# Display.net
KiCad netlist of a schematic drawn in Altium Designer
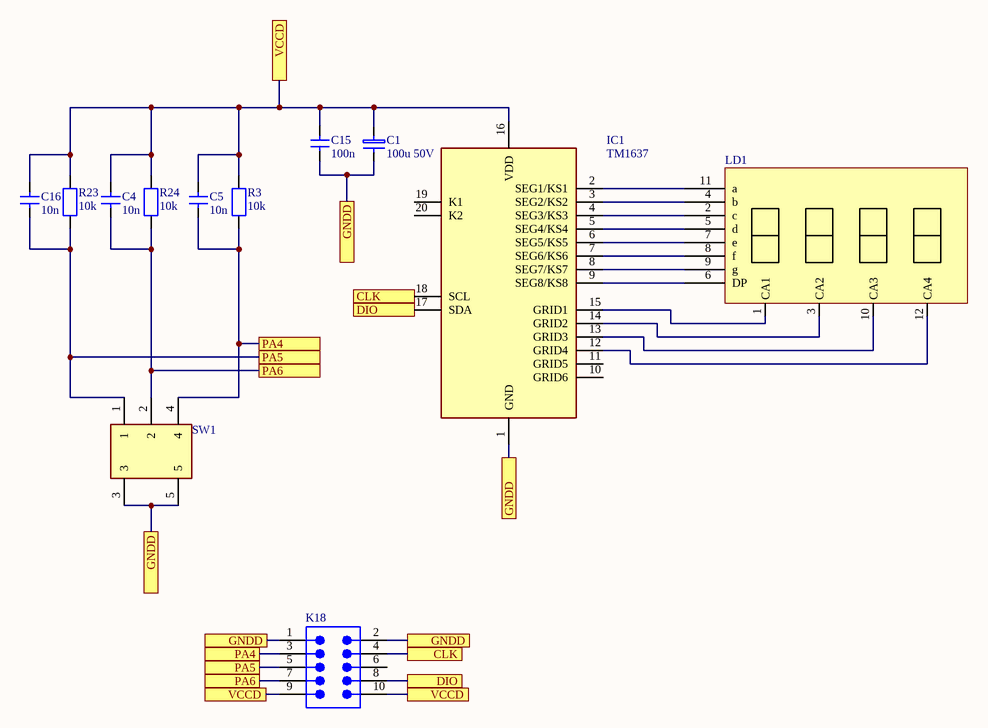
[diagram p0: Display.SchDoc]

(export (version "E")
  (design (tool "Eeschema 10.0.6"))
  (components
    (comp (ref "C1")
      (value "100u 50V")
      (footprint "CAPACITOR100UF")
      (description "860010683032 WCAP-ATG8 Aluminum Electrolytic Capacitors")
      (fields (field (name "TOLERANCE") "20%"))
      (libsource (lib "Soldeerstation Schematic") (part "CapacitorPol"))
    )
    (comp (ref "C4")
      (value "10n")
      (footprint "CAPACITOR10NF")
      (description "CAP CER 10000PF 50V X7R 0805")
      (fields (field (name "TOLERANCE") "10%"))
      (libsource (lib "Soldeerstation Schematic") (part "Capacitor"))
    )
    (comp (ref "C5")
      (value "10n")
      (footprint "CAPACITOR10NF")
      (description "CAP CER 10000PF 50V X7R 0805")
      (fields (field (name "TOLERANCE") "10%"))
      (libsource (lib "Soldeerstation Schematic") (part "Capacitor"))
    )
    (comp (ref "C15")
      (value "100n")
      (footprint "Capacitor100nf")
      (description "CAP CER 10000PF 50V X7R 0805")
      (fields (field (name "TOLERANCE") "10%"))
      (libsource (lib "Soldeerstation Schematic") (part "Capacitor"))
    )
    (comp (ref "C16")
      (value "10n")
      (footprint "CAPACITOR10NF")
      (description "CAP CER 10000PF 50V X7R 0805")
      (fields (field (name "TOLERANCE") "10%"))
      (libsource (lib "Soldeerstation Schematic") (part "Capacitor"))
    )
    (comp (ref "IC1")
      (value "TM1637")
      (footprint "Soldeerstation PCB:TM1637")
      (description "LED Drive Control Special Circuit")
      (fields (field (name "MF") "Titan Micro Electronics"))
      (libsource (lib "Soldeerstation Schematic") (part "TM1637"))
    )
    (comp (ref "K18")
      (value "61231020621")
      (footprint "[10][2]Pinheader")
      (libsource (lib "Soldeerstation Schematic") (part "[10][2]Pinheader"))
    )
    (comp (ref "LD1")
      (value "~")
      (footprint "7segment")
      (libsource (lib "Soldeerstation Schematic") (part "7segment"))
    )
    (comp (ref "R3")
      (value "10k")
      (footprint "Resistor")
      (fields (field (name "MANUFACTURER") "Vishay Dale") (field (name "PART NUMBER") "CRCW08050000Z0EA"))
      (libsource (lib "Soldeerstation Schematic") (part "Resistor"))
    )
    (comp (ref "R23")
      (value "10k")
      (footprint "Resistor")
      (fields (field (name "MANUFACTURER") "Vishay Dale") (field (name "PART NUMBER") "CRCW08050000Z0EA"))
      (libsource (lib "Soldeerstation Schematic") (part "Resistor"))
    )
    (comp (ref "R24")
      (value "10k")
      (footprint "Resistor")
      (fields (field (name "MANUFACTURER") "Vishay Dale") (field (name "PART NUMBER") "CRCW08050000Z0EA"))
      (libsource (lib "Soldeerstation Schematic") (part "Resistor"))
    )
    (comp (ref "SW1")
      (value "~")
      (footprint "Soldeerstation PCB:Encoder")
      (description "Undefined or Miscellaneous")
      (fields
        (field (name "MOUSER2 PART NUMBER") "652-PEC11R-4225F-S24")
        (field (name "MANUFACTURER_PART_NUMBER") "PEC11R-4225F-S0024")
      )
      (libsource (lib "Soldeerstation Schematic") (part "Encoder"))
    )
  )
  (nets
    (net (code "1") (name "/CLK") (class "Default")
      (node (ref "IC1") (pin "18") (pinfunction "SCL_18") (pintype "passive"))
      (node (ref "K18") (pin "4") (pinfunction "4_4") (pintype "passive"))
    )
    (net (code "2") (name "/DIO") (class "Default")
      (node (ref "IC1") (pin "17") (pinfunction "SDA_17") (pintype "passive"))
      (node (ref "K18") (pin "8") (pinfunction "8_8") (pintype "passive"))
    )
    (net (code "3") (name "/GNDD") (class "Default")
      (node (ref "C1") (pin "2") (pinfunction "2_2") (pintype "passive"))
      (node (ref "C15") (pin "1") (pinfunction "1_1") (pintype "passive"))
      (node (ref "IC1") (pin "1") (pinfunction "GND_1") (pintype "power_in"))
      (node (ref "K18") (pin "1") (pinfunction "1_1") (pintype "passive"))
      (node (ref "K18") (pin "2") (pinfunction "2_2") (pintype "passive"))
      (node (ref "SW1") (pin "3") (pinfunction "3_3") (pintype "passive"))
      (node (ref "SW1") (pin "5") (pinfunction "5_5") (pintype "passive"))
    )
    (net (code "4") (name "/PA4") (class "Default")
      (node (ref "C5") (pin "1") (pinfunction "1_1") (pintype "passive"))
      (node (ref "K18") (pin "3") (pinfunction "3_3") (pintype "passive"))
      (node (ref "R3") (pin "1") (pinfunction "1_1") (pintype "passive"))
      (node (ref "SW1") (pin "4") (pinfunction "4_4") (pintype "passive"))
    )
    (net (code "5") (name "/PA5") (class "Default")
      (node (ref "C16") (pin "1") (pinfunction "1_1") (pintype "passive"))
      (node (ref "K18") (pin "5") (pinfunction "5_5") (pintype "passive"))
      (node (ref "R23") (pin "1") (pinfunction "1_1") (pintype "passive"))
      (node (ref "SW1") (pin "1") (pinfunction "1_1") (pintype "passive"))
    )
    (net (code "6") (name "/PA6") (class "Default")
      (node (ref "C4") (pin "1") (pinfunction "1_1") (pintype "passive"))
      (node (ref "K18") (pin "7") (pinfunction "7_7") (pintype "passive"))
      (node (ref "R24") (pin "1") (pinfunction "1_1") (pintype "passive"))
      (node (ref "SW1") (pin "2") (pinfunction "2_2") (pintype "passive"))
    )
    (net (code "7") (name "/VCCD") (class "Default")
      (node (ref "C1") (pin "1") (pinfunction "1_1") (pintype "passive"))
      (node (ref "C15") (pin "2") (pinfunction "2_2") (pintype "passive"))
      (node (ref "C16") (pin "2") (pinfunction "2_2") (pintype "passive"))
      (node (ref "C4") (pin "2") (pinfunction "2_2") (pintype "passive"))
      (node (ref "C5") (pin "2") (pinfunction "2_2") (pintype "passive"))
      (node (ref "IC1") (pin "16") (pinfunction "VDD_16") (pintype "power_in"))
      (node (ref "K18") (pin "10") (pinfunction "10_10") (pintype "passive"))
      (node (ref "K18") (pin "9") (pinfunction "9_9") (pintype "passive"))
      (node (ref "R23") (pin "2") (pinfunction "2_2") (pintype "passive"))
      (node (ref "R24") (pin "2") (pinfunction "2_2") (pintype "passive"))
      (node (ref "R3") (pin "2") (pinfunction "2_2") (pintype "passive"))
    )
    (net (code "8") (name "Net-(IC1-GRID1)") (class "Default")
      (node (ref "IC1") (pin "15") (pinfunction "GRID1_15") (pintype "passive"))
      (node (ref "LD1") (pin "1") (pinfunction "CA1_1") (pintype "passive"))
    )
    (net (code "9") (name "Net-(IC1-GRID2)") (class "Default")
      (node (ref "IC1") (pin "14") (pinfunction "GRID2_14") (pintype "passive"))
      (node (ref "LD1") (pin "3") (pinfunction "CA2_3") (pintype "passive"))
    )
    (net (code "10") (name "Net-(IC1-GRID3)") (class "Default")
      (node (ref "IC1") (pin "13") (pinfunction "GRID3_13") (pintype "passive"))
      (node (ref "LD1") (pin "10") (pinfunction "CA3_10") (pintype "passive"))
    )
    (net (code "11") (name "Net-(IC1-GRID4)") (class "Default")
      (node (ref "IC1") (pin "12") (pinfunction "GRID4_12") (pintype "passive"))
      (node (ref "LD1") (pin "12") (pinfunction "CA4_12") (pintype "passive"))
    )
    (net (code "12") (name "Net-(IC1-SEG1{slash}KS1)") (class "Default")
      (node (ref "IC1") (pin "2") (pinfunction "SEG1/KS1_2") (pintype "passive"))
      (node (ref "LD1") (pin "11") (pinfunction "a_11") (pintype "passive"))
    )
    (net (code "13") (name "Net-(IC1-SEG2{slash}KS2)") (class "Default")
      (node (ref "IC1") (pin "3") (pinfunction "SEG2/KS2_3") (pintype "passive"))
      (node (ref "LD1") (pin "4") (pinfunction "b_4") (pintype "passive"))
    )
    (net (code "14") (name "Net-(IC1-SEG3{slash}KS3)") (class "Default")
      (node (ref "IC1") (pin "4") (pinfunction "SEG3/KS3_4") (pintype "passive"))
      (node (ref "LD1") (pin "2") (pinfunction "c_2") (pintype "passive"))
    )
    (net (code "15") (name "Net-(IC1-SEG4{slash}KS4)") (class "Default")
      (node (ref "IC1") (pin "5") (pinfunction "SEG4/KS4_5") (pintype "passive"))
      (node (ref "LD1") (pin "5") (pinfunction "d_5") (pintype "passive"))
    )
    (net (code "16") (name "Net-(IC1-SEG5{slash}KS5)") (class "Default")
      (node (ref "IC1") (pin "6") (pinfunction "SEG5/KS5_6") (pintype "passive"))
      (node (ref "LD1") (pin "7") (pinfunction "e_7") (pintype "passive"))
    )
    (net (code "17") (name "Net-(IC1-SEG6{slash}KS6)") (class "Default")
      (node (ref "IC1") (pin "7") (pinfunction "SEG6/KS6_7") (pintype "passive"))
      (node (ref "LD1") (pin "8") (pinfunction "f_8") (pintype "passive"))
    )
    (net (code "18") (name "Net-(IC1-SEG7{slash}KS7)") (class "Default")
      (node (ref "IC1") (pin "8") (pinfunction "SEG7/KS7_8") (pintype "passive"))
      (node (ref "LD1") (pin "9") (pinfunction "g_9") (pintype "passive"))
    )
    (net (code "19") (name "Net-(IC1-SEG8{slash}KS8)") (class "Default")
      (node (ref "IC1") (pin "9") (pinfunction "SEG8/KS8_9") (pintype "passive"))
      (node (ref "LD1") (pin "6") (pinfunction "DP_6") (pintype "power_in"))
    )
    (net (code "20") (name "unconnected-(IC1-GRID5-Pad11)") (class "Default")
      (node (ref "IC1") (pin "11") (pinfunction "GRID5_11") (pintype "passive"))
    )
    (net (code "21") (name "unconnected-(IC1-GRID6-Pad10)") (class "Default")
      (node (ref "IC1") (pin "10") (pinfunction "GRID6_10") (pintype "passive"))
    )
    (net (code "22") (name "unconnected-(IC1-K1-Pad19)") (class "Default")
      (node (ref "IC1") (pin "19") (pinfunction "K1_19") (pintype "passive"))
    )
    (net (code "23") (name "unconnected-(IC1-K2-Pad20)") (class "Default")
      (node (ref "IC1") (pin "20") (pinfunction "K2_20") (pintype "passive"))
    )
    (net (code "24") (name "unconnected-(K18-Pad6)") (class "Default")
      (node (ref "K18") (pin "6") (pinfunction "6_6") (pintype "passive"))
    )
  )
)
